# Light_Sensors.net
KiCad netlist of a schematic drawn in EAGLE
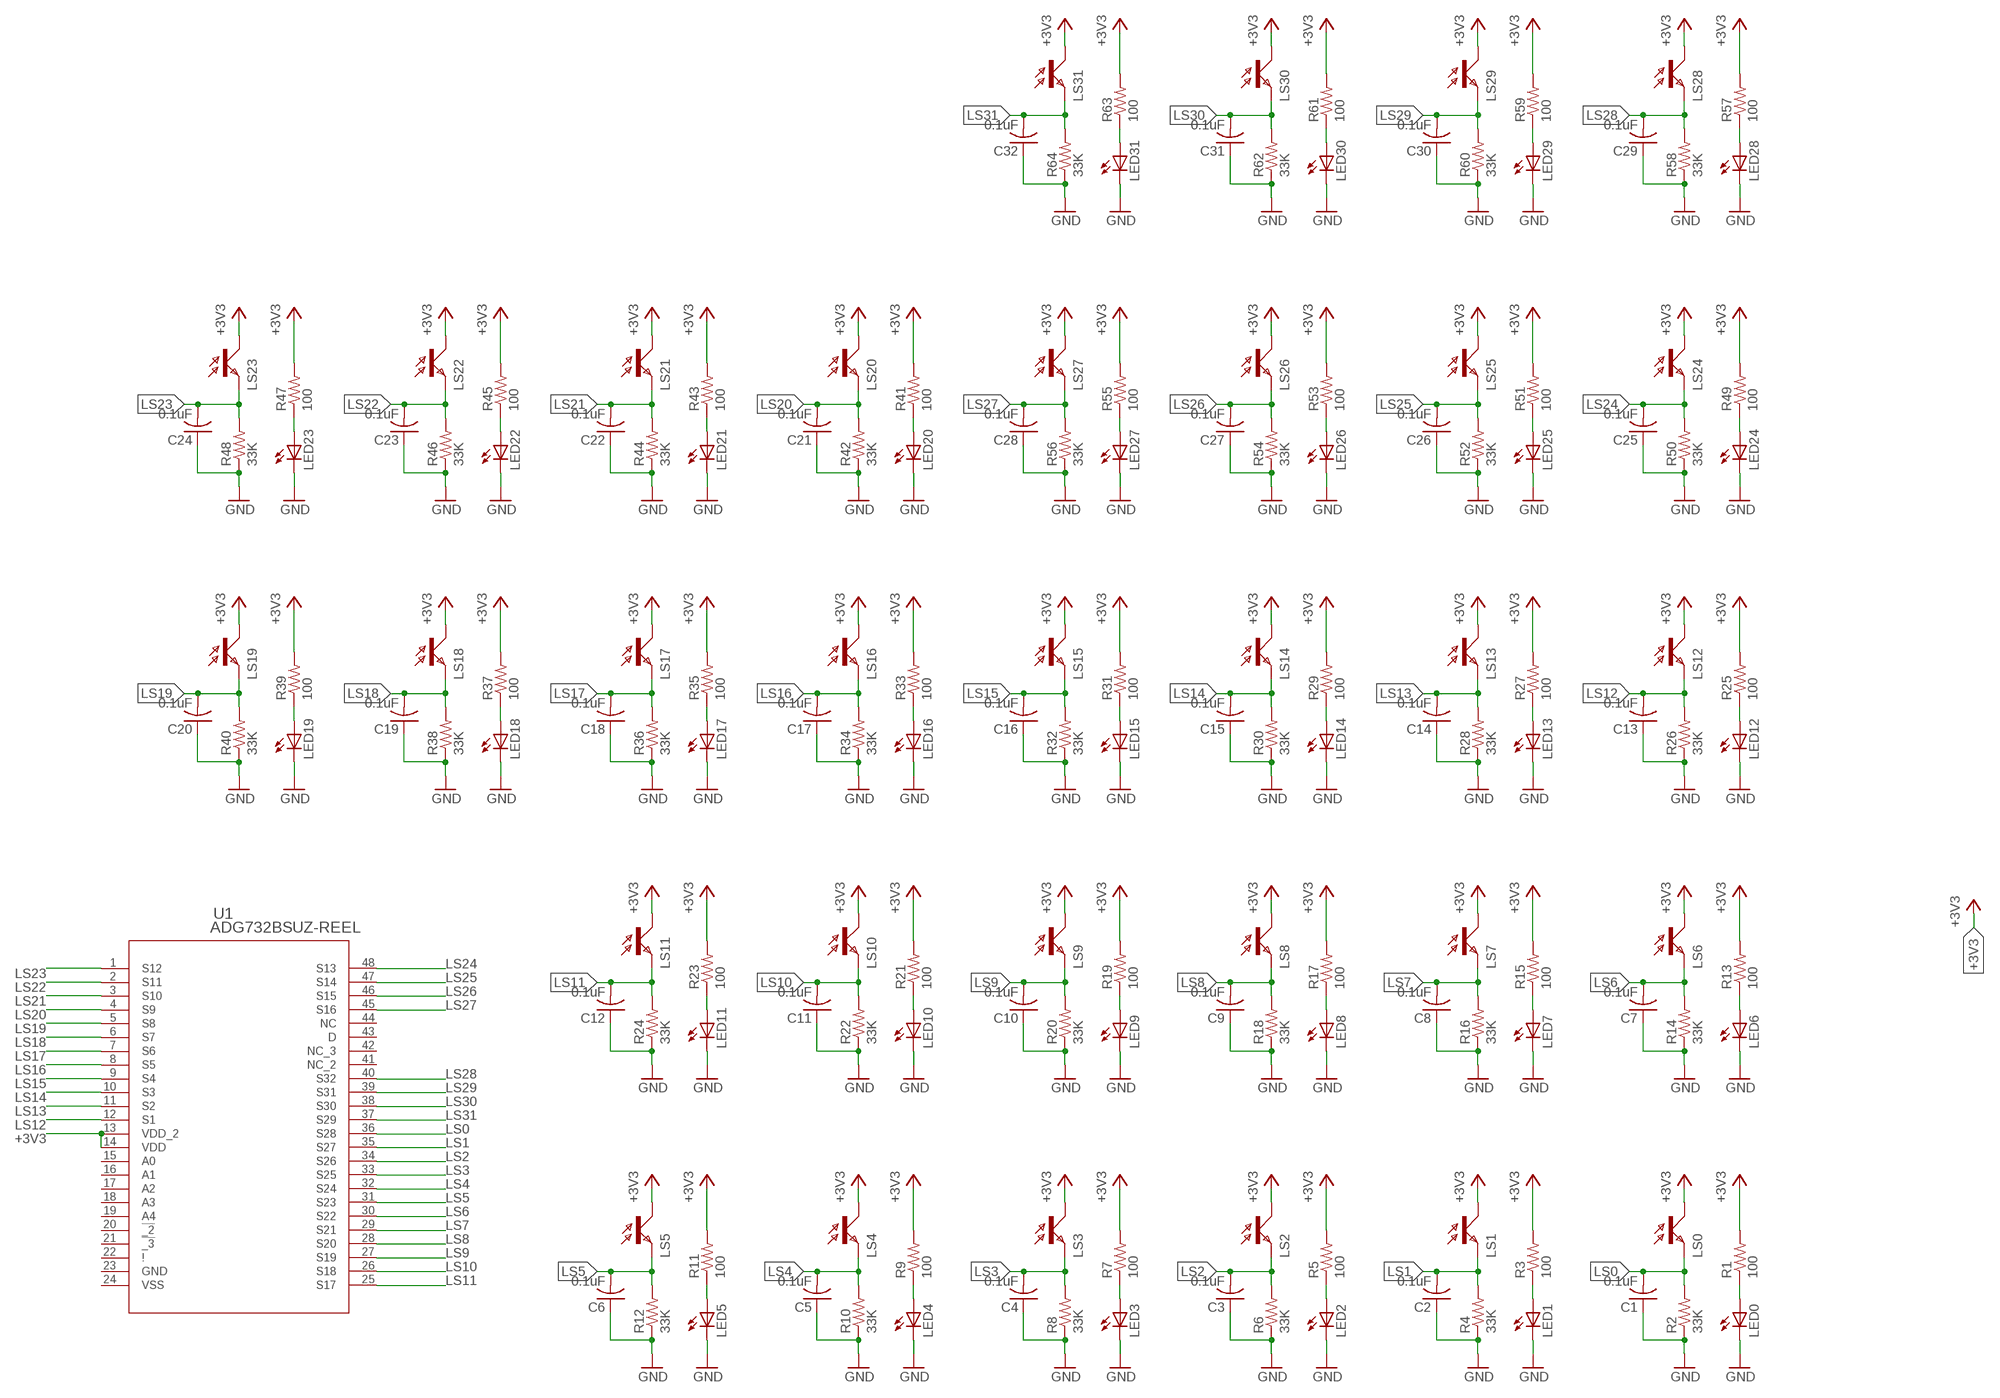
[diagram p0: schematic, sheet 1]

(export (version "E")
  (design (tool "Eeschema 10.0.6"))
  (components
    (comp (ref "C1")
      (value "0.1uF")
      (footprint "eagle-import:C0603")
      (libsource (lib "eagle-import") (part "C-USC0603"))
    )
    (comp (ref "C2")
      (value "0.1uF")
      (footprint "eagle-import:C0603")
      (libsource (lib "eagle-import") (part "C-USC0603"))
    )
    (comp (ref "C3")
      (value "0.1uF")
      (footprint "eagle-import:C0603")
      (libsource (lib "eagle-import") (part "C-USC0603"))
    )
    (comp (ref "C4")
      (value "0.1uF")
      (footprint "eagle-import:C0603")
      (libsource (lib "eagle-import") (part "C-USC0603"))
    )
    (comp (ref "C5")
      (value "0.1uF")
      (footprint "eagle-import:C0603")
      (libsource (lib "eagle-import") (part "C-USC0603"))
    )
    (comp (ref "C6")
      (value "0.1uF")
      (footprint "eagle-import:C0603")
      (libsource (lib "eagle-import") (part "C-USC0603"))
    )
    (comp (ref "C7")
      (value "0.1uF")
      (footprint "eagle-import:C0603")
      (libsource (lib "eagle-import") (part "C-USC0603"))
    )
    (comp (ref "C8")
      (value "0.1uF")
      (footprint "eagle-import:C0603")
      (libsource (lib "eagle-import") (part "C-USC0603"))
    )
    (comp (ref "C9")
      (value "0.1uF")
      (footprint "eagle-import:C0603")
      (libsource (lib "eagle-import") (part "C-USC0603"))
    )
    (comp (ref "C10")
      (value "0.1uF")
      (footprint "eagle-import:C0603")
      (libsource (lib "eagle-import") (part "C-USC0603"))
    )
    (comp (ref "C11")
      (value "0.1uF")
      (footprint "eagle-import:C0603")
      (libsource (lib "eagle-import") (part "C-USC0603"))
    )
    (comp (ref "C12")
      (value "0.1uF")
      (footprint "eagle-import:C0603")
      (libsource (lib "eagle-import") (part "C-USC0603"))
    )
    (comp (ref "C13")
      (value "0.1uF")
      (footprint "eagle-import:C0603")
      (libsource (lib "eagle-import") (part "C-USC0603"))
    )
    (comp (ref "C14")
      (value "0.1uF")
      (footprint "eagle-import:C0603")
      (libsource (lib "eagle-import") (part "C-USC0603"))
    )
    (comp (ref "C15")
      (value "0.1uF")
      (footprint "eagle-import:C0603")
      (libsource (lib "eagle-import") (part "C-USC0603"))
    )
    (comp (ref "C16")
      (value "0.1uF")
      (footprint "eagle-import:C0603")
      (libsource (lib "eagle-import") (part "C-USC0603"))
    )
    (comp (ref "C17")
      (value "0.1uF")
      (footprint "eagle-import:C0603")
      (libsource (lib "eagle-import") (part "C-USC0603"))
    )
    (comp (ref "C18")
      (value "0.1uF")
      (footprint "eagle-import:C0603")
      (libsource (lib "eagle-import") (part "C-USC0603"))
    )
    (comp (ref "C19")
      (value "0.1uF")
      (footprint "eagle-import:C0603")
      (libsource (lib "eagle-import") (part "C-USC0603"))
    )
    (comp (ref "C20")
      (value "0.1uF")
      (footprint "eagle-import:C0603")
      (libsource (lib "eagle-import") (part "C-USC0603"))
    )
    (comp (ref "C21")
      (value "0.1uF")
      (footprint "eagle-import:C0603")
      (libsource (lib "eagle-import") (part "C-USC0603"))
    )
    (comp (ref "C22")
      (value "0.1uF")
      (footprint "eagle-import:C0603")
      (libsource (lib "eagle-import") (part "C-USC0603"))
    )
    (comp (ref "C23")
      (value "0.1uF")
      (footprint "eagle-import:C0603")
      (libsource (lib "eagle-import") (part "C-USC0603"))
    )
    (comp (ref "C24")
      (value "0.1uF")
      (footprint "eagle-import:C0603")
      (libsource (lib "eagle-import") (part "C-USC0603"))
    )
    (comp (ref "C25")
      (value "0.1uF")
      (footprint "eagle-import:C0603")
      (libsource (lib "eagle-import") (part "C-USC0603"))
    )
    (comp (ref "C26")
      (value "0.1uF")
      (footprint "eagle-import:C0603")
      (libsource (lib "eagle-import") (part "C-USC0603"))
    )
    (comp (ref "C27")
      (value "0.1uF")
      (footprint "eagle-import:C0603")
      (libsource (lib "eagle-import") (part "C-USC0603"))
    )
    (comp (ref "C28")
      (value "0.1uF")
      (footprint "eagle-import:C0603")
      (libsource (lib "eagle-import") (part "C-USC0603"))
    )
    (comp (ref "C29")
      (value "0.1uF")
      (footprint "eagle-import:C0603")
      (libsource (lib "eagle-import") (part "C-USC0603"))
    )
    (comp (ref "C30")
      (value "0.1uF")
      (footprint "eagle-import:C0603")
      (libsource (lib "eagle-import") (part "C-USC0603"))
    )
    (comp (ref "C31")
      (value "0.1uF")
      (footprint "eagle-import:C0603")
      (libsource (lib "eagle-import") (part "C-USC0603"))
    )
    (comp (ref "C32")
      (value "0.1uF")
      (footprint "eagle-import:C0603")
      (libsource (lib "eagle-import") (part "C-USC0603"))
    )
    (comp (ref "LED0")
      (value "LEDCHIPLED_0603")
      (footprint "eagle-import:CHIPLED_0603")
      (libsource (lib "eagle-import") (part "LEDCHIPLED_0603"))
    )
    (comp (ref "LED1")
      (value "LEDCHIPLED_0603")
      (footprint "eagle-import:CHIPLED_0603")
      (libsource (lib "eagle-import") (part "LEDCHIPLED_0603"))
    )
    (comp (ref "LED2")
      (value "LEDCHIPLED_0603")
      (footprint "eagle-import:CHIPLED_0603")
      (libsource (lib "eagle-import") (part "LEDCHIPLED_0603"))
    )
    (comp (ref "LED3")
      (value "LEDCHIPLED_0603")
      (footprint "eagle-import:CHIPLED_0603")
      (libsource (lib "eagle-import") (part "LEDCHIPLED_0603"))
    )
    (comp (ref "LED4")
      (value "LEDCHIPLED_0603")
      (footprint "eagle-import:CHIPLED_0603")
      (libsource (lib "eagle-import") (part "LEDCHIPLED_0603"))
    )
    (comp (ref "LED5")
      (value "LEDCHIPLED_0603")
      (footprint "eagle-import:CHIPLED_0603")
      (libsource (lib "eagle-import") (part "LEDCHIPLED_0603"))
    )
    (comp (ref "LED6")
      (value "LEDCHIPLED_0603")
      (footprint "eagle-import:CHIPLED_0603")
      (libsource (lib "eagle-import") (part "LEDCHIPLED_0603"))
    )
    (comp (ref "LED7")
      (value "LEDCHIPLED_0603")
      (footprint "eagle-import:CHIPLED_0603")
      (libsource (lib "eagle-import") (part "LEDCHIPLED_0603"))
    )
    (comp (ref "LED8")
      (value "LEDCHIPLED_0603")
      (footprint "eagle-import:CHIPLED_0603")
      (libsource (lib "eagle-import") (part "LEDCHIPLED_0603"))
    )
    (comp (ref "LED9")
      (value "LEDCHIPLED_0603")
      (footprint "eagle-import:CHIPLED_0603")
      (libsource (lib "eagle-import") (part "LEDCHIPLED_0603"))
    )
    (comp (ref "LED10")
      (value "LEDCHIPLED_0603")
      (footprint "eagle-import:CHIPLED_0603")
      (libsource (lib "eagle-import") (part "LEDCHIPLED_0603"))
    )
    (comp (ref "LED11")
      (value "LEDCHIPLED_0603")
      (footprint "eagle-import:CHIPLED_0603")
      (libsource (lib "eagle-import") (part "LEDCHIPLED_0603"))
    )
    (comp (ref "LED12")
      (value "LEDCHIPLED_0603")
      (footprint "eagle-import:CHIPLED_0603")
      (libsource (lib "eagle-import") (part "LEDCHIPLED_0603"))
    )
    (comp (ref "LED13")
      (value "LEDCHIPLED_0603")
      (footprint "eagle-import:CHIPLED_0603")
      (libsource (lib "eagle-import") (part "LEDCHIPLED_0603"))
    )
    (comp (ref "LED14")
      (value "LEDCHIPLED_0603")
      (footprint "eagle-import:CHIPLED_0603")
      (libsource (lib "eagle-import") (part "LEDCHIPLED_0603"))
    )
    (comp (ref "LED15")
      (value "LEDCHIPLED_0603")
      (footprint "eagle-import:CHIPLED_0603")
      (libsource (lib "eagle-import") (part "LEDCHIPLED_0603"))
    )
    (comp (ref "LED16")
      (value "LEDCHIPLED_0603")
      (footprint "eagle-import:CHIPLED_0603")
      (libsource (lib "eagle-import") (part "LEDCHIPLED_0603"))
    )
    (comp (ref "LED17")
      (value "LEDCHIPLED_0603")
      (footprint "eagle-import:CHIPLED_0603")
      (libsource (lib "eagle-import") (part "LEDCHIPLED_0603"))
    )
    (comp (ref "LED18")
      (value "LEDCHIPLED_0603")
      (footprint "eagle-import:CHIPLED_0603")
      (libsource (lib "eagle-import") (part "LEDCHIPLED_0603"))
    )
    (comp (ref "LED19")
      (value "LEDCHIPLED_0603")
      (footprint "eagle-import:CHIPLED_0603")
      (libsource (lib "eagle-import") (part "LEDCHIPLED_0603"))
    )
    (comp (ref "LED20")
      (value "LEDCHIPLED_0603")
      (footprint "eagle-import:CHIPLED_0603")
      (libsource (lib "eagle-import") (part "LEDCHIPLED_0603"))
    )
    (comp (ref "LED21")
      (value "LEDCHIPLED_0603")
      (footprint "eagle-import:CHIPLED_0603")
      (libsource (lib "eagle-import") (part "LEDCHIPLED_0603"))
    )
    (comp (ref "LED22")
      (value "LEDCHIPLED_0603")
      (footprint "eagle-import:CHIPLED_0603")
      (libsource (lib "eagle-import") (part "LEDCHIPLED_0603"))
    )
    (comp (ref "LED23")
      (value "LEDCHIPLED_0603")
      (footprint "eagle-import:CHIPLED_0603")
      (libsource (lib "eagle-import") (part "LEDCHIPLED_0603"))
    )
    (comp (ref "LED24")
      (value "LEDCHIPLED_0603")
      (footprint "eagle-import:CHIPLED_0603")
      (libsource (lib "eagle-import") (part "LEDCHIPLED_0603"))
    )
    (comp (ref "LED25")
      (value "LEDCHIPLED_0603")
      (footprint "eagle-import:CHIPLED_0603")
      (libsource (lib "eagle-import") (part "LEDCHIPLED_0603"))
    )
    (comp (ref "LED26")
      (value "LEDCHIPLED_0603")
      (footprint "eagle-import:CHIPLED_0603")
      (libsource (lib "eagle-import") (part "LEDCHIPLED_0603"))
    )
    (comp (ref "LED27")
      (value "LEDCHIPLED_0603")
      (footprint "eagle-import:CHIPLED_0603")
      (libsource (lib "eagle-import") (part "LEDCHIPLED_0603"))
    )
    (comp (ref "LED28")
      (value "LEDCHIPLED_0603")
      (footprint "eagle-import:CHIPLED_0603")
      (libsource (lib "eagle-import") (part "LEDCHIPLED_0603"))
    )
    (comp (ref "LED29")
      (value "LEDCHIPLED_0603")
      (footprint "eagle-import:CHIPLED_0603")
      (libsource (lib "eagle-import") (part "LEDCHIPLED_0603"))
    )
    (comp (ref "LED30")
      (value "LEDCHIPLED_0603")
      (footprint "eagle-import:CHIPLED_0603")
      (libsource (lib "eagle-import") (part "LEDCHIPLED_0603"))
    )
    (comp (ref "LED31")
      (value "LEDCHIPLED_0603")
      (footprint "eagle-import:CHIPLED_0603")
      (libsource (lib "eagle-import") (part "LEDCHIPLED_0603"))
    )
    (comp (ref "LS0")
      (value "ALS")
      (footprint "eagle-import:SMD")
      (libsource (lib "eagle-import") (part "ALS"))
    )
    (comp (ref "LS1")
      (value "ALS")
      (footprint "eagle-import:SMD")
      (libsource (lib "eagle-import") (part "ALS"))
    )
    (comp (ref "LS2")
      (value "ALS")
      (footprint "eagle-import:SMD")
      (libsource (lib "eagle-import") (part "ALS"))
    )
    (comp (ref "LS3")
      (value "ALS")
      (footprint "eagle-import:SMD")
      (libsource (lib "eagle-import") (part "ALS"))
    )
    (comp (ref "LS4")
      (value "ALS")
      (footprint "eagle-import:SMD")
      (libsource (lib "eagle-import") (part "ALS"))
    )
    (comp (ref "LS5")
      (value "ALS")
      (footprint "eagle-import:SMD")
      (libsource (lib "eagle-import") (part "ALS"))
    )
    (comp (ref "LS6")
      (value "ALS")
      (footprint "eagle-import:SMD")
      (libsource (lib "eagle-import") (part "ALS"))
    )
    (comp (ref "LS7")
      (value "ALS")
      (footprint "eagle-import:SMD")
      (libsource (lib "eagle-import") (part "ALS"))
    )
    (comp (ref "LS8")
      (value "ALS")
      (footprint "eagle-import:SMD")
      (libsource (lib "eagle-import") (part "ALS"))
    )
    (comp (ref "LS9")
      (value "ALS")
      (footprint "eagle-import:SMD")
      (libsource (lib "eagle-import") (part "ALS"))
    )
    (comp (ref "LS10")
      (value "ALS")
      (footprint "eagle-import:SMD")
      (libsource (lib "eagle-import") (part "ALS"))
    )
    (comp (ref "LS11")
      (value "ALS")
      (footprint "eagle-import:SMD")
      (libsource (lib "eagle-import") (part "ALS"))
    )
    (comp (ref "LS12")
      (value "ALS")
      (footprint "eagle-import:SMD")
      (libsource (lib "eagle-import") (part "ALS"))
    )
    (comp (ref "LS13")
      (value "ALS")
      (footprint "eagle-import:SMD")
      (libsource (lib "eagle-import") (part "ALS"))
    )
    (comp (ref "LS14")
      (value "ALS")
      (footprint "eagle-import:SMD")
      (libsource (lib "eagle-import") (part "ALS"))
    )
    (comp (ref "LS15")
      (value "ALS")
      (footprint "eagle-import:SMD")
      (libsource (lib "eagle-import") (part "ALS"))
    )
    (comp (ref "LS16")
      (value "ALS")
      (footprint "eagle-import:SMD")
      (libsource (lib "eagle-import") (part "ALS"))
    )
    (comp (ref "LS17")
      (value "ALS")
      (footprint "eagle-import:SMD")
      (libsource (lib "eagle-import") (part "ALS"))
    )
    (comp (ref "LS18")
      (value "ALS")
      (footprint "eagle-import:SMD")
      (libsource (lib "eagle-import") (part "ALS"))
    )
    (comp (ref "LS19")
      (value "ALS")
      (footprint "eagle-import:SMD")
      (libsource (lib "eagle-import") (part "ALS"))
    )
    (comp (ref "LS20")
      (value "ALS")
      (footprint "eagle-import:SMD")
      (libsource (lib "eagle-import") (part "ALS"))
    )
    (comp (ref "LS21")
      (value "ALS")
      (footprint "eagle-import:SMD")
      (libsource (lib "eagle-import") (part "ALS"))
    )
    (comp (ref "LS22")
      (value "ALS")
      (footprint "eagle-import:SMD")
      (libsource (lib "eagle-import") (part "ALS"))
    )
    (comp (ref "LS23")
      (value "ALS")
      (footprint "eagle-import:SMD")
      (libsource (lib "eagle-import") (part "ALS"))
    )
    (comp (ref "LS24")
      (value "ALS")
      (footprint "eagle-import:SMD")
      (libsource (lib "eagle-import") (part "ALS"))
    )
    (comp (ref "LS25")
      (value "ALS")
      (footprint "eagle-import:SMD")
      (libsource (lib "eagle-import") (part "ALS"))
    )
    (comp (ref "LS26")
      (value "ALS")
      (footprint "eagle-import:SMD")
      (libsource (lib "eagle-import") (part "ALS"))
    )
    (comp (ref "LS27")
      (value "ALS")
      (footprint "eagle-import:SMD")
      (libsource (lib "eagle-import") (part "ALS"))
    )
    (comp (ref "LS28")
      (value "ALS")
      (footprint "eagle-import:SMD")
      (libsource (lib "eagle-import") (part "ALS"))
    )
    (comp (ref "LS29")
      (value "ALS")
      (footprint "eagle-import:SMD")
      (libsource (lib "eagle-import") (part "ALS"))
    )
    (comp (ref "LS30")
      (value "ALS")
      (footprint "eagle-import:SMD")
      (libsource (lib "eagle-import") (part "ALS"))
    )
    (comp (ref "LS31")
      (value "ALS")
      (footprint "eagle-import:SMD")
      (libsource (lib "eagle-import") (part "ALS"))
    )
    (comp (ref "R1")
      (value "100")
      (footprint "eagle-import:R0603")
      (libsource (lib "eagle-import") (part "R-US_R0603"))
    )
    (comp (ref "R2")
      (value "33K")
      (footprint "eagle-import:R0603")
      (libsource (lib "eagle-import") (part "R-US_R0603"))
    )
    (comp (ref "R3")
      (value "100")
      (footprint "eagle-import:R0603")
      (libsource (lib "eagle-import") (part "R-US_R0603"))
    )
    (comp (ref "R4")
      (value "33K")
      (footprint "eagle-import:R0603")
      (libsource (lib "eagle-import") (part "R-US_R0603"))
    )
    (comp (ref "R5")
      (value "100")
      (footprint "eagle-import:R0603")
      (libsource (lib "eagle-import") (part "R-US_R0603"))
    )
    (comp (ref "R6")
      (value "33K")
      (footprint "eagle-import:R0603")
      (libsource (lib "eagle-import") (part "R-US_R0603"))
    )
    (comp (ref "R7")
      (value "100")
      (footprint "eagle-import:R0603")
      (libsource (lib "eagle-import") (part "R-US_R0603"))
    )
    (comp (ref "R8")
      (value "33K")
      (footprint "eagle-import:R0603")
      (libsource (lib "eagle-import") (part "R-US_R0603"))
    )
    (comp (ref "R9")
      (value "100")
      (footprint "eagle-import:R0603")
      (libsource (lib "eagle-import") (part "R-US_R0603"))
    )
    (comp (ref "R10")
      (value "33K")
      (footprint "eagle-import:R0603")
      (libsource (lib "eagle-import") (part "R-US_R0603"))
    )
    (comp (ref "R11")
      (value "100")
      (footprint "eagle-import:R0603")
      (libsource (lib "eagle-import") (part "R-US_R0603"))
    )
    (comp (ref "R12")
      (value "33K")
      (footprint "eagle-import:R0603")
      (libsource (lib "eagle-import") (part "R-US_R0603"))
    )
    (comp (ref "R13")
      (value "100")
      (footprint "eagle-import:R0603")
      (libsource (lib "eagle-import") (part "R-US_R0603"))
    )
    (comp (ref "R14")
      (value "33K")
      (footprint "eagle-import:R0603")
      (libsource (lib "eagle-import") (part "R-US_R0603"))
    )
    (comp (ref "R15")
      (value "100")
      (footprint "eagle-import:R0603")
      (libsource (lib "eagle-import") (part "R-US_R0603"))
    )
    (comp (ref "R16")
      (value "33K")
      (footprint "eagle-import:R0603")
      (libsource (lib "eagle-import") (part "R-US_R0603"))
    )
    (comp (ref "R17")
      (value "100")
      (footprint "eagle-import:R0603")
      (libsource (lib "eagle-import") (part "R-US_R0603"))
    )
    (comp (ref "R18")
      (value "33K")
      (footprint "eagle-import:R0603")
      (libsource (lib "eagle-import") (part "R-US_R0603"))
    )
    (comp (ref "R19")
      (value "100")
      (footprint "eagle-import:R0603")
      (libsource (lib "eagle-import") (part "R-US_R0603"))
    )
    (comp (ref "R20")
      (value "33K")
      (footprint "eagle-import:R0603")
      (libsource (lib "eagle-import") (part "R-US_R0603"))
    )
    (comp (ref "R21")
      (value "100")
      (footprint "eagle-import:R0603")
      (libsource (lib "eagle-import") (part "R-US_R0603"))
    )
    (comp (ref "R22")
      (value "33K")
      (footprint "eagle-import:R0603")
      (libsource (lib "eagle-import") (part "R-US_R0603"))
    )
    (comp (ref "R23")
      (value "100")
      (footprint "eagle-import:R0603")
      (libsource (lib "eagle-import") (part "R-US_R0603"))
    )
    (comp (ref "R24")
      (value "33K")
      (footprint "eagle-import:R0603")
      (libsource (lib "eagle-import") (part "R-US_R0603"))
    )
    (comp (ref "R25")
      (value "100")
      (footprint "eagle-import:R0603")
      (libsource (lib "eagle-import") (part "R-US_R0603"))
    )
    (comp (ref "R26")
      (value "33K")
      (footprint "eagle-import:R0603")
      (libsource (lib "eagle-import") (part "R-US_R0603"))
    )
    (comp (ref "R27")
      (value "100")
      (footprint "eagle-import:R0603")
      (libsource (lib "eagle-import") (part "R-US_R0603"))
    )
    (comp (ref "R28")
      (value "33K")
      (footprint "eagle-import:R0603")
      (libsource (lib "eagle-import") (part "R-US_R0603"))
    )
    (comp (ref "R29")
      (value "100")
      (footprint "eagle-import:R0603")
      (libsource (lib "eagle-import") (part "R-US_R0603"))
    )
    (comp (ref "R30")
      (value "33K")
      (footprint "eagle-import:R0603")
      (libsource (lib "eagle-import") (part "R-US_R0603"))
    )
    (comp (ref "R31")
      (value "100")
      (footprint "eagle-import:R0603")
      (libsource (lib "eagle-import") (part "R-US_R0603"))
    )
    (comp (ref "R32")
      (value "33K")
      (footprint "eagle-import:R0603")
      (libsource (lib "eagle-import") (part "R-US_R0603"))
    )
    (comp (ref "R33")
      (value "100")
      (footprint "eagle-import:R0603")
      (libsource (lib "eagle-import") (part "R-US_R0603"))
    )
    (comp (ref "R34")
      (value "33K")
      (footprint "eagle-import:R0603")
      (libsource (lib "eagle-import") (part "R-US_R0603"))
    )
    (comp (ref "R35")
      (value "100")
      (footprint "eagle-import:R0603")
      (libsource (lib "eagle-import") (part "R-US_R0603"))
    )
    (comp (ref "R36")
      (value "33K")
      (footprint "eagle-import:R0603")
      (libsource (lib "eagle-import") (part "R-US_R0603"))
    )
    (comp (ref "R37")
      (value "100")
      (footprint "eagle-import:R0603")
      (libsource (lib "eagle-import") (part "R-US_R0603"))
    )
    (comp (ref "R38")
      (value "33K")
      (footprint "eagle-import:R0603")
      (libsource (lib "eagle-import") (part "R-US_R0603"))
    )
    (comp (ref "R39")
      (value "100")
      (footprint "eagle-import:R0603")
      (libsource (lib "eagle-import") (part "R-US_R0603"))
    )
    (comp (ref "R40")
      (value "33K")
      (footprint "eagle-import:R0603")
      (libsource (lib "eagle-import") (part "R-US_R0603"))
    )
    (comp (ref "R41")
      (value "100")
      (footprint "eagle-import:R0603")
      (libsource (lib "eagle-import") (part "R-US_R0603"))
    )
    (comp (ref "R42")
      (value "33K")
      (footprint "eagle-import:R0603")
      (libsource (lib "eagle-import") (part "R-US_R0603"))
    )
    (comp (ref "R43")
      (value "100")
      (footprint "eagle-import:R0603")
      (libsource (lib "eagle-import") (part "R-US_R0603"))
    )
    (comp (ref "R44")
      (value "33K")
      (footprint "eagle-import:R0603")
      (libsource (lib "eagle-import") (part "R-US_R0603"))
    )
    (comp (ref "R45")
      (value "100")
      (footprint "eagle-import:R0603")
      (libsource (lib "eagle-import") (part "R-US_R0603"))
    )
    (comp (ref "R46")
      (value "33K")
      (footprint "eagle-import:R0603")
      (libsource (lib "eagle-import") (part "R-US_R0603"))
    )
    (comp (ref "R47")
      (value "100")
      (footprint "eagle-import:R0603")
      (libsource (lib "eagle-import") (part "R-US_R0603"))
    )
    (comp (ref "R48")
      (value "33K")
      (footprint "eagle-import:R0603")
      (libsource (lib "eagle-import") (part "R-US_R0603"))
    )
    (comp (ref "R49")
      (value "100")
      (footprint "eagle-import:R0603")
      (libsource (lib "eagle-import") (part "R-US_R0603"))
    )
    (comp (ref "R50")
      (value "33K")
      (footprint "eagle-import:R0603")
      (libsource (lib "eagle-import") (part "R-US_R0603"))
    )
    (comp (ref "R51")
      (value "100")
      (footprint "eagle-import:R0603")
      (libsource (lib "eagle-import") (part "R-US_R0603"))
    )
    (comp (ref "R52")
      (value "33K")
      (footprint "eagle-import:R0603")
      (libsource (lib "eagle-import") (part "R-US_R0603"))
    )
    (comp (ref "R53")
      (value "100")
      (footprint "eagle-import:R0603")
      (libsource (lib "eagle-import") (part "R-US_R0603"))
    )
    (comp (ref "R54")
      (value "33K")
      (footprint "eagle-import:R0603")
      (libsource (lib "eagle-import") (part "R-US_R0603"))
    )
    (comp (ref "R55")
      (value "100")
      (footprint "eagle-import:R0603")
      (libsource (lib "eagle-import") (part "R-US_R0603"))
    )
    (comp (ref "R56")
      (value "33K")
      (footprint "eagle-import:R0603")
      (libsource (lib "eagle-import") (part "R-US_R0603"))
    )
    (comp (ref "R57")
      (value "100")
      (footprint "eagle-import:R0603")
      (libsource (lib "eagle-import") (part "R-US_R0603"))
    )
    (comp (ref "R58")
      (value "33K")
      (footprint "eagle-import:R0603")
      (libsource (lib "eagle-import") (part "R-US_R0603"))
    )
    (comp (ref "R59")
      (value "100")
      (footprint "eagle-import:R0603")
      (libsource (lib "eagle-import") (part "R-US_R0603"))
    )
    (comp (ref "R60")
      (value "33K")
      (footprint "eagle-import:R0603")
      (libsource (lib "eagle-import") (part "R-US_R0603"))
    )
    (comp (ref "R61")
      (value "100")
      (footprint "eagle-import:R0603")
      (libsource (lib "eagle-import") (part "R-US_R0603"))
    )
    (comp (ref "R62")
      (value "33K")
      (footprint "eagle-import:R0603")
      (libsource (lib "eagle-import") (part "R-US_R0603"))
    )
    (comp (ref "R63")
      (value "100")
      (footprint "eagle-import:R0603")
      (libsource (lib "eagle-import") (part "R-US_R0603"))
    )
    (comp (ref "R64")
      (value "33K")
      (footprint "eagle-import:R0603")
      (libsource (lib "eagle-import") (part "R-US_R0603"))
    )
    (comp (ref "U1")
      (value "ADG732BSUZ-REEL")
      (footprint "eagle-import:SU_48")
      (fields (field (name "MANUFACTURER_PART_NUMBER") "ADG732BSUZREEL"))
      (libsource (lib "eagle-import") (part "ADG732BSUZ-REEL"))
    )
  )
  (nets
    (net (code "1") (name "+3V3") (class "Default")
      (node (ref "LS0") (pin "C") (pinfunction "C_C") (pintype "passive"))
      (node (ref "LS1") (pin "C") (pinfunction "C_C") (pintype "passive"))
      (node (ref "LS10") (pin "C") (pinfunction "C_C") (pintype "passive"))
      (node (ref "LS11") (pin "C") (pinfunction "C_C") (pintype "passive"))
      (node (ref "LS12") (pin "C") (pinfunction "C_C") (pintype "passive"))
      (node (ref "LS13") (pin "C") (pinfunction "C_C") (pintype "passive"))
      (node (ref "LS14") (pin "C") (pinfunction "C_C") (pintype "passive"))
      (node (ref "LS15") (pin "C") (pinfunction "C_C") (pintype "passive"))
      (node (ref "LS16") (pin "C") (pinfunction "C_C") (pintype "passive"))
      (node (ref "LS17") (pin "C") (pinfunction "C_C") (pintype "passive"))
      (node (ref "LS18") (pin "C") (pinfunction "C_C") (pintype "passive"))
      (node (ref "LS19") (pin "C") (pinfunction "C_C") (pintype "passive"))
      (node (ref "LS2") (pin "C") (pinfunction "C_C") (pintype "passive"))
      (node (ref "LS20") (pin "C") (pinfunction "C_C") (pintype "passive"))
      (node (ref "LS21") (pin "C") (pinfunction "C_C") (pintype "passive"))
      (node (ref "LS22") (pin "C") (pinfunction "C_C") (pintype "passive"))
      (node (ref "LS23") (pin "C") (pinfunction "C_C") (pintype "passive"))
      (node (ref "LS24") (pin "C") (pinfunction "C_C") (pintype "passive"))
      (node (ref "LS25") (pin "C") (pinfunction "C_C") (pintype "passive"))
      (node (ref "LS26") (pin "C") (pinfunction "C_C") (pintype "passive"))
      (node (ref "LS27") (pin "C") (pinfunction "C_C") (pintype "passive"))
      (node (ref "LS28") (pin "C") (pinfunction "C_C") (pintype "passive"))
      (node (ref "LS29") (pin "C") (pinfunction "C_C") (pintype "passive"))
      (node (ref "LS3") (pin "C") (pinfunction "C_C") (pintype "passive"))
      (node (ref "LS30") (pin "C") (pinfunction "C_C") (pintype "passive"))
      (node (ref "LS31") (pin "C") (pinfunction "C_C") (pintype "passive"))
      (node (ref "LS4") (pin "C") (pinfunction "C_C") (pintype "passive"))
      (node (ref "LS5") (pin "C") (pinfunction "C_C") (pintype "passive"))
      (node (ref "LS6") (pin "C") (pinfunction "C_C") (pintype "passive"))
      (node (ref "LS7") (pin "C") (pinfunction "C_C") (pintype "passive"))
      (node (ref "LS8") (pin "C") (pinfunction "C_C") (pintype "passive"))
      (node (ref "LS9") (pin "C") (pinfunction "C_C") (pintype "passive"))
      (node (ref "R1") (pin "2") (pinfunction "2_2") (pintype "passive"))
      (node (ref "R11") (pin "2") (pinfunction "2_2") (pintype "passive"))
      (node (ref "R13") (pin "2") (pinfunction "2_2") (pintype "passive"))
      (node (ref "R15") (pin "2") (pinfunction "2_2") (pintype "passive"))
      (node (ref "R17") (pin "2") (pinfunction "2_2") (pintype "passive"))
      (node (ref "R19") (pin "2") (pinfunction "2_2") (pintype "passive"))
      (node (ref "R21") (pin "2") (pinfunction "2_2") (pintype "passive"))
      (node (ref "R23") (pin "2") (pinfunction "2_2") (pintype "passive"))
      (node (ref "R25") (pin "2") (pinfunction "2_2") (pintype "passive"))
      (node (ref "R27") (pin "2") (pinfunction "2_2") (pintype "passive"))
      (node (ref "R29") (pin "2") (pinfunction "2_2") (pintype "passive"))
      (node (ref "R3") (pin "2") (pinfunction "2_2") (pintype "passive"))
      (node (ref "R31") (pin "2") (pinfunction "2_2") (pintype "passive"))
      (node (ref "R33") (pin "2") (pinfunction "2_2") (pintype "passive"))
      (node (ref "R35") (pin "2") (pinfunction "2_2") (pintype "passive"))
      (node (ref "R37") (pin "2") (pinfunction "2_2") (pintype "passive"))
      (node (ref "R39") (pin "2") (pinfunction "2_2") (pintype "passive"))
      (node (ref "R41") (pin "2") (pinfunction "2_2") (pintype "passive"))
      (node (ref "R43") (pin "2") (pinfunction "2_2") (pintype "passive"))
      (node (ref "R45") (pin "2") (pinfunction "2_2") (pintype "passive"))
      (node (ref "R47") (pin "2") (pinfunction "2_2") (pintype "passive"))
      (node (ref "R49") (pin "2") (pinfunction "2_2") (pintype "passive"))
      (node (ref "R5") (pin "2") (pinfunction "2_2") (pintype "passive"))
      (node (ref "R51") (pin "2") (pinfunction "2_2") (pintype "passive"))
      (node (ref "R53") (pin "2") (pinfunction "2_2") (pintype "passive"))
      (node (ref "R55") (pin "2") (pinfunction "2_2") (pintype "passive"))
      (node (ref "R57") (pin "2") (pinfunction "2_2") (pintype "passive"))
      (node (ref "R59") (pin "2") (pinfunction "2_2") (pintype "passive"))
      (node (ref "R61") (pin "2") (pinfunction "2_2") (pintype "passive"))
      (node (ref "R63") (pin "2") (pinfunction "2_2") (pintype "passive"))
      (node (ref "R7") (pin "2") (pinfunction "2_2") (pintype "passive"))
      (node (ref "R9") (pin "2") (pinfunction "2_2") (pintype "passive"))
      (node (ref "U1") (pin "13") (pinfunction "VDD_2_13") (pintype "power_in"))
      (node (ref "U1") (pin "14") (pinfunction "VDD_14") (pintype "power_in"))
    )
    (net (code "2") (name "/VSS") (class "Default")
      (node (ref "U1") (pin "24") (pinfunction "VSS_24") (pintype "power_in"))
    )
    (net (code "3") (name "GND") (class "Default")
      (node (ref "C1") (pin "1") (pinfunction "1_1") (pintype "passive"))
      (node (ref "C10") (pin "1") (pinfunction "1_1") (pintype "passive"))
      (node (ref "C11") (pin "1") (pinfunction "1_1") (pintype "passive"))
      (node (ref "C12") (pin "1") (pinfunction "1_1") (pintype "passive"))
      (node (ref "C13") (pin "1") (pinfunction "1_1") (pintype "passive"))
      (node (ref "C14") (pin "1") (pinfunction "1_1") (pintype "passive"))
      (node (ref "C15") (pin "1") (pinfunction "1_1") (pintype "passive"))
      (node (ref "C16") (pin "1") (pinfunction "1_1") (pintype "passive"))
      (node (ref "C17") (pin "1") (pinfunction "1_1") (pintype "passive"))
      (node (ref "C18") (pin "1") (pinfunction "1_1") (pintype "passive"))
      (node (ref "C19") (pin "1") (pinfunction "1_1") (pintype "passive"))
      (node (ref "C2") (pin "1") (pinfunction "1_1") (pintype "passive"))
      (node (ref "C20") (pin "1") (pinfunction "1_1") (pintype "passive"))
      (node (ref "C21") (pin "1") (pinfunction "1_1") (pintype "passive"))
      (node (ref "C22") (pin "1") (pinfunction "1_1") (pintype "passive"))
      (node (ref "C23") (pin "1") (pinfunction "1_1") (pintype "passive"))
      (node (ref "C24") (pin "1") (pinfunction "1_1") (pintype "passive"))
      (node (ref "C25") (pin "1") (pinfunction "1_1") (pintype "passive"))
      (node (ref "C26") (pin "1") (pinfunction "1_1") (pintype "passive"))
      (node (ref "C27") (pin "1") (pinfunction "1_1") (pintype "passive"))
      (node (ref "C28") (pin "1") (pinfunction "1_1") (pintype "passive"))
      (node (ref "C29") (pin "1") (pinfunction "1_1") (pintype "passive"))
      (node (ref "C3") (pin "1") (pinfunction "1_1") (pintype "passive"))
      (node (ref "C30") (pin "1") (pinfunction "1_1") (pintype "passive"))
      (node (ref "C31") (pin "1") (pinfunction "1_1") (pintype "passive"))
      (node (ref "C32") (pin "1") (pinfunction "1_1") (pintype "passive"))
      (node (ref "C4") (pin "1") (pinfunction "1_1") (pintype "passive"))
      (node (ref "C5") (pin "1") (pinfunction "1_1") (pintype "passive"))
      (node (ref "C6") (pin "1") (pinfunction "1_1") (pintype "passive"))
      (node (ref "C7") (pin "1") (pinfunction "1_1") (pintype "passive"))
      (node (ref "C8") (pin "1") (pinfunction "1_1") (pintype "passive"))
      (node (ref "C9") (pin "1") (pinfunction "1_1") (pintype "passive"))
      (node (ref "LED0") (pin "C") (pinfunction "C_C") (pintype "passive"))
      (node (ref "LED1") (pin "C") (pinfunction "C_C") (pintype "passive"))
      (node (ref "LED10") (pin "C") (pinfunction "C_C") (pintype "passive"))
      (node (ref "LED11") (pin "C") (pinfunction "C_C") (pintype "passive"))
      (node (ref "LED12") (pin "C") (pinfunction "C_C") (pintype "passive"))
      (node (ref "LED13") (pin "C") (pinfunction "C_C") (pintype "passive"))
      (node (ref "LED14") (pin "C") (pinfunction "C_C") (pintype "passive"))
      (node (ref "LED15") (pin "C") (pinfunction "C_C") (pintype "passive"))
      (node (ref "LED16") (pin "C") (pinfunction "C_C") (pintype "passive"))
      (node (ref "LED17") (pin "C") (pinfunction "C_C") (pintype "passive"))
      (node (ref "LED18") (pin "C") (pinfunction "C_C") (pintype "passive"))
      (node (ref "LED19") (pin "C") (pinfunction "C_C") (pintype "passive"))
      (node (ref "LED2") (pin "C") (pinfunction "C_C") (pintype "passive"))
      (node (ref "LED20") (pin "C") (pinfunction "C_C") (pintype "passive"))
      (node (ref "LED21") (pin "C") (pinfunction "C_C") (pintype "passive"))
      (node (ref "LED22") (pin "C") (pinfunction "C_C") (pintype "passive"))
      (node (ref "LED23") (pin "C") (pinfunction "C_C") (pintype "passive"))
      (node (ref "LED24") (pin "C") (pinfunction "C_C") (pintype "passive"))
      (node (ref "LED25") (pin "C") (pinfunction "C_C") (pintype "passive"))
      (node (ref "LED26") (pin "C") (pinfunction "C_C") (pintype "passive"))
      (node (ref "LED27") (pin "C") (pinfunction "C_C") (pintype "passive"))
      (node (ref "LED28") (pin "C") (pinfunction "C_C") (pintype "passive"))
      (node (ref "LED29") (pin "C") (pinfunction "C_C") (pintype "passive"))
      (node (ref "LED3") (pin "C") (pinfunction "C_C") (pintype "passive"))
      (node (ref "LED30") (pin "C") (pinfunction "C_C") (pintype "passive"))
      (node (ref "LED31") (pin "C") (pinfunction "C_C") (pintype "passive"))
      (node (ref "LED4") (pin "C") (pinfunction "C_C") (pintype "passive"))
      (node (ref "LED5") (pin "C") (pinfunction "C_C") (pintype "passive"))
      (node (ref "LED6") (pin "C") (pinfunction "C_C") (pintype "passive"))
      (node (ref "LED7") (pin "C") (pinfunction "C_C") (pintype "passive"))
      (node (ref "LED8") (pin "C") (pinfunction "C_C") (pintype "passive"))
      (node (ref "LED9") (pin "C") (pinfunction "C_C") (pintype "passive"))
      (node (ref "R10") (pin "1") (pinfunction "1_1") (pintype "passive"))
      (node (ref "R12") (pin "1") (pinfunction "1_1") (pintype "passive"))
      (node (ref "R14") (pin "1") (pinfunction "1_1") (pintype "passive"))
      (node (ref "R16") (pin "1") (pinfunction "1_1") (pintype "passive"))
      (node (ref "R18") (pin "1") (pinfunction "1_1") (pintype "passive"))
      (node (ref "R2") (pin "1") (pinfunction "1_1") (pintype "passive"))
      (node (ref "R20") (pin "1") (pinfunction "1_1") (pintype "passive"))
      (node (ref "R22") (pin "1") (pinfunction "1_1") (pintype "passive"))
      (node (ref "R24") (pin "1") (pinfunction "1_1") (pintype "passive"))
      (node (ref "R26") (pin "1") (pinfunction "1_1") (pintype "passive"))
      (node (ref "R28") (pin "1") (pinfunction "1_1") (pintype "passive"))
      (node (ref "R30") (pin "1") (pinfunction "1_1") (pintype "passive"))
      (node (ref "R32") (pin "1") (pinfunction "1_1") (pintype "passive"))
      (node (ref "R34") (pin "1") (pinfunction "1_1") (pintype "passive"))
      (node (ref "R36") (pin "1") (pinfunction "1_1") (pintype "passive"))
      (node (ref "R38") (pin "1") (pinfunction "1_1") (pintype "passive"))
      (node (ref "R4") (pin "1") (pinfunction "1_1") (pintype "passive"))
      (node (ref "R40") (pin "1") (pinfunction "1_1") (pintype "passive"))
      (node (ref "R42") (pin "1") (pinfunction "1_1") (pintype "passive"))
      (node (ref "R44") (pin "1") (pinfunction "1_1") (pintype "passive"))
      (node (ref "R46") (pin "1") (pinfunction "1_1") (pintype "passive"))
      (node (ref "R48") (pin "1") (pinfunction "1_1") (pintype "passive"))
      (node (ref "R50") (pin "1") (pinfunction "1_1") (pintype "passive"))
      (node (ref "R52") (pin "1") (pinfunction "1_1") (pintype "passive"))
      (node (ref "R54") (pin "1") (pinfunction "1_1") (pintype "passive"))
      (node (ref "R56") (pin "1") (pinfunction "1_1") (pintype "passive"))
      (node (ref "R58") (pin "1") (pinfunction "1_1") (pintype "passive"))
      (node (ref "R6") (pin "1") (pinfunction "1_1") (pintype "passive"))
      (node (ref "R60") (pin "1") (pinfunction "1_1") (pintype "passive"))
      (node (ref "R62") (pin "1") (pinfunction "1_1") (pintype "passive"))
      (node (ref "R64") (pin "1") (pinfunction "1_1") (pintype "passive"))
      (node (ref "R8") (pin "1") (pinfunction "1_1") (pintype "passive"))
    )
    (net (code "4") (name "LS0") (class "Default")
      (node (ref "C1") (pin "2") (pinfunction "2_2") (pintype "passive"))
      (node (ref "LS0") (pin "E") (pinfunction "E_E") (pintype "passive"))
      (node (ref "R2") (pin "2") (pinfunction "2_2") (pintype "passive"))
      (node (ref "U1") (pin "36") (pinfunction "S28_36") (pintype "passive"))
    )
    (net (code "5") (name "LS1") (class "Default")
      (node (ref "C2") (pin "2") (pinfunction "2_2") (pintype "passive"))
      (node (ref "LS1") (pin "E") (pinfunction "E_E") (pintype "passive"))
      (node (ref "R4") (pin "2") (pinfunction "2_2") (pintype "passive"))
      (node (ref "U1") (pin "35") (pinfunction "S27_35") (pintype "passive"))
    )
    (net (code "6") (name "LS2") (class "Default")
      (node (ref "C3") (pin "2") (pinfunction "2_2") (pintype "passive"))
      (node (ref "LS2") (pin "E") (pinfunction "E_E") (pintype "passive"))
      (node (ref "R6") (pin "2") (pinfunction "2_2") (pintype "passive"))
      (node (ref "U1") (pin "34") (pinfunction "S26_34") (pintype "passive"))
    )
    (net (code "7") (name "LS3") (class "Default")
      (node (ref "C4") (pin "2") (pinfunction "2_2") (pintype "passive"))
      (node (ref "LS3") (pin "E") (pinfunction "E_E") (pintype "passive"))
      (node (ref "R8") (pin "2") (pinfunction "2_2") (pintype "passive"))
      (node (ref "U1") (pin "33") (pinfunction "S25_33") (pintype "passive"))
    )
    (net (code "8") (name "LS4") (class "Default")
      (node (ref "C5") (pin "2") (pinfunction "2_2") (pintype "passive"))
      (node (ref "LS4") (pin "E") (pinfunction "E_E") (pintype "passive"))
      (node (ref "R10") (pin "2") (pinfunction "2_2") (pintype "passive"))
      (node (ref "U1") (pin "32") (pinfunction "S24_32") (pintype "passive"))
    )
    (net (code "9") (name "LS5") (class "Default")
      (node (ref "C6") (pin "2") (pinfunction "2_2") (pintype "passive"))
      (node (ref "LS5") (pin "E") (pinfunction "E_E") (pintype "passive"))
      (node (ref "R12") (pin "2") (pinfunction "2_2") (pintype "passive"))
      (node (ref "U1") (pin "31") (pinfunction "S23_31") (pintype "passive"))
    )
    (net (code "10") (name "LS6") (class "Default")
      (node (ref "C7") (pin "2") (pinfunction "2_2") (pintype "passive"))
      (node (ref "LS6") (pin "E") (pinfunction "E_E") (pintype "passive"))
      (node (ref "R14") (pin "2") (pinfunction "2_2") (pintype "passive"))
      (node (ref "U1") (pin "30") (pinfunction "S22_30") (pintype "passive"))
    )
    (net (code "11") (name "LS7") (class "Default")
      (node (ref "C8") (pin "2") (pinfunction "2_2") (pintype "passive"))
      (node (ref "LS7") (pin "E") (pinfunction "E_E") (pintype "passive"))
      (node (ref "R16") (pin "2") (pinfunction "2_2") (pintype "passive"))
      (node (ref "U1") (pin "29") (pinfunction "S21_29") (pintype "passive"))
    )
    (net (code "12") (name "LS8") (class "Default")
      (node (ref "C9") (pin "2") (pinfunction "2_2") (pintype "passive"))
      (node (ref "LS8") (pin "E") (pinfunction "E_E") (pintype "passive"))
      (node (ref "R18") (pin "2") (pinfunction "2_2") (pintype "passive"))
      (node (ref "U1") (pin "28") (pinfunction "S20_28") (pintype "passive"))
    )
    (net (code "13") (name "LS9") (class "Default")
      (node (ref "C10") (pin "2") (pinfunction "2_2") (pintype "passive"))
      (node (ref "LS9") (pin "E") (pinfunction "E_E") (pintype "passive"))
      (node (ref "R20") (pin "2") (pinfunction "2_2") (pintype "passive"))
      (node (ref "U1") (pin "27") (pinfunction "S19_27") (pintype "passive"))
    )
    (net (code "14") (name "LS10") (class "Default")
      (node (ref "C11") (pin "2") (pinfunction "2_2") (pintype "passive"))
      (node (ref "LS10") (pin "E") (pinfunction "E_E") (pintype "passive"))
      (node (ref "R22") (pin "2") (pinfunction "2_2") (pintype "passive"))
      (node (ref "U1") (pin "26") (pinfunction "S18_26") (pintype "passive"))
    )
    (net (code "15") (name "LS11") (class "Default")
      (node (ref "C12") (pin "2") (pinfunction "2_2") (pintype "passive"))
      (node (ref "LS11") (pin "E") (pinfunction "E_E") (pintype "passive"))
      (node (ref "R24") (pin "2") (pinfunction "2_2") (pintype "passive"))
      (node (ref "U1") (pin "25") (pinfunction "S17_25") (pintype "passive"))
    )
    (net (code "16") (name "LS12") (class "Default")
      (node (ref "C13") (pin "2") (pinfunction "2_2") (pintype "passive"))
      (node (ref "LS12") (pin "E") (pinfunction "E_E") (pintype "passive"))
      (node (ref "R26") (pin "2") (pinfunction "2_2") (pintype "passive"))
      (node (ref "U1") (pin "12") (pinfunction "S1_12") (pintype "passive"))
    )
    (net (code "17") (name "LS13") (class "Default")
      (node (ref "C14") (pin "2") (pinfunction "2_2") (pintype "passive"))
      (node (ref "LS13") (pin "E") (pinfunction "E_E") (pintype "passive"))
      (node (ref "R28") (pin "2") (pinfunction "2_2") (pintype "passive"))
      (node (ref "U1") (pin "11") (pinfunction "S2_11") (pintype "passive"))
    )
    (net (code "18") (name "LS14") (class "Default")
      (node (ref "C15") (pin "2") (pinfunction "2_2") (pintype "passive"))
      (node (ref "LS14") (pin "E") (pinfunction "E_E") (pintype "passive"))
      (node (ref "R30") (pin "2") (pinfunction "2_2") (pintype "passive"))
      (node (ref "U1") (pin "10") (pinfunction "S3_10") (pintype "passive"))
    )
    (net (code "19") (name "LS15") (class "Default")
      (node (ref "C16") (pin "2") (pinfunction "2_2") (pintype "passive"))
      (node (ref "LS15") (pin "E") (pinfunction "E_E") (pintype "passive"))
      (node (ref "R32") (pin "2") (pinfunction "2_2") (pintype "passive"))
      (node (ref "U1") (pin "9") (pinfunction "S4_9") (pintype "passive"))
    )
    (net (code "20") (name "LS16") (class "Default")
      (node (ref "C17") (pin "2") (pinfunction "2_2") (pintype "passive"))
      (node (ref "LS16") (pin "E") (pinfunction "E_E") (pintype "passive"))
      (node (ref "R34") (pin "2") (pinfunction "2_2") (pintype "passive"))
      (node (ref "U1") (pin "8") (pinfunction "S5_8") (pintype "passive"))
    )
    (net (code "21") (name "LS17") (class "Default")
      (node (ref "C18") (pin "2") (pinfunction "2_2") (pintype "passive"))
      (node (ref "LS17") (pin "E") (pinfunction "E_E") (pintype "passive"))
      (node (ref "R36") (pin "2") (pinfunction "2_2") (pintype "passive"))
      (node (ref "U1") (pin "7") (pinfunction "S6_7") (pintype "passive"))
    )
    (net (code "22") (name "LS18") (class "Default")
      (node (ref "C19") (pin "2") (pinfunction "2_2") (pintype "passive"))
      (node (ref "LS18") (pin "E") (pinfunction "E_E") (pintype "passive"))
      (node (ref "R38") (pin "2") (pinfunction "2_2") (pintype "passive"))
      (node (ref "U1") (pin "6") (pinfunction "S7_6") (pintype "passive"))
    )
    (net (code "23") (name "LS19") (class "Default")
      (node (ref "C20") (pin "2") (pinfunction "2_2") (pintype "passive"))
      (node (ref "LS19") (pin "E") (pinfunction "E_E") (pintype "passive"))
      (node (ref "R40") (pin "2") (pinfunction "2_2") (pintype "passive"))
      (node (ref "U1") (pin "5") (pinfunction "S8_5") (pintype "passive"))
    )
    (net (code "24") (name "LS20") (class "Default")
      (node (ref "C21") (pin "2") (pinfunction "2_2") (pintype "passive"))
      (node (ref "LS20") (pin "E") (pinfunction "E_E") (pintype "passive"))
      (node (ref "R42") (pin "2") (pinfunction "2_2") (pintype "passive"))
      (node (ref "U1") (pin "4") (pinfunction "S9_4") (pintype "passive"))
    )
    (net (code "25") (name "LS21") (class "Default")
      (node (ref "C22") (pin "2") (pinfunction "2_2") (pintype "passive"))
      (node (ref "LS21") (pin "E") (pinfunction "E_E") (pintype "passive"))
      (node (ref "R44") (pin "2") (pinfunction "2_2") (pintype "passive"))
      (node (ref "U1") (pin "3") (pinfunction "S10_3") (pintype "passive"))
    )
    (net (code "26") (name "LS22") (class "Default")
      (node (ref "C23") (pin "2") (pinfunction "2_2") (pintype "passive"))
      (node (ref "LS22") (pin "E") (pinfunction "E_E") (pintype "passive"))
      (node (ref "R46") (pin "2") (pinfunction "2_2") (pintype "passive"))
      (node (ref "U1") (pin "2") (pinfunction "S11_2") (pintype "passive"))
    )
    (net (code "27") (name "LS23") (class "Default")
      (node (ref "C24") (pin "2") (pinfunction "2_2") (pintype "passive"))
      (node (ref "LS23") (pin "E") (pinfunction "E_E") (pintype "passive"))
      (node (ref "R48") (pin "2") (pinfunction "2_2") (pintype "passive"))
      (node (ref "U1") (pin "1") (pinfunction "S12_1") (pintype "passive"))
    )
    (net (code "28") (name "LS24") (class "Default")
      (node (ref "C25") (pin "2") (pinfunction "2_2") (pintype "passive"))
      (node (ref "LS24") (pin "E") (pinfunction "E_E") (pintype "passive"))
      (node (ref "R50") (pin "2") (pinfunction "2_2") (pintype "passive"))
      (node (ref "U1") (pin "48") (pinfunction "S13_48") (pintype "passive"))
    )
    (net (code "29") (name "LS25") (class "Default")
      (node (ref "C26") (pin "2") (pinfunction "2_2") (pintype "passive"))
      (node (ref "LS25") (pin "E") (pinfunction "E_E") (pintype "passive"))
      (node (ref "R52") (pin "2") (pinfunction "2_2") (pintype "passive"))
      (node (ref "U1") (pin "47") (pinfunction "S14_47") (pintype "passive"))
    )
    (net (code "30") (name "LS26") (class "Default")
      (node (ref "C27") (pin "2") (pinfunction "2_2") (pintype "passive"))
      (node (ref "LS26") (pin "E") (pinfunction "E_E") (pintype "passive"))
      (node (ref "R54") (pin "2") (pinfunction "2_2") (pintype "passive"))
      (node (ref "U1") (pin "46") (pinfunction "S15_46") (pintype "passive"))
    )
    (net (code "31") (name "LS27") (class "Default")
      (node (ref "C28") (pin "2") (pinfunction "2_2") (pintype "passive"))
      (node (ref "LS27") (pin "E") (pinfunction "E_E") (pintype "passive"))
      (node (ref "R56") (pin "2") (pinfunction "2_2") (pintype "passive"))
      (node (ref "U1") (pin "45") (pinfunction "S16_45") (pintype "passive"))
    )
    (net (code "32") (name "LS28") (class "Default")
      (node (ref "C29") (pin "2") (pinfunction "2_2") (pintype "passive"))
      (node (ref "LS28") (pin "E") (pinfunction "E_E") (pintype "passive"))
      (node (ref "R58") (pin "2") (pinfunction "2_2") (pintype "passive"))
      (node (ref "U1") (pin "40") (pinfunction "S32_40") (pintype "passive"))
    )
    (net (code "33") (name "LS29") (class "Default")
      (node (ref "C30") (pin "2") (pinfunction "2_2") (pintype "passive"))
      (node (ref "LS29") (pin "E") (pinfunction "E_E") (pintype "passive"))
      (node (ref "R60") (pin "2") (pinfunction "2_2") (pintype "passive"))
      (node (ref "U1") (pin "39") (pinfunction "S31_39") (pintype "passive"))
    )
    (net (code "34") (name "LS30") (class "Default")
      (node (ref "C31") (pin "2") (pinfunction "2_2") (pintype "passive"))
      (node (ref "LS30") (pin "E") (pinfunction "E_E") (pintype "passive"))
      (node (ref "R62") (pin "2") (pinfunction "2_2") (pintype "passive"))
      (node (ref "U1") (pin "38") (pinfunction "S30_38") (pintype "passive"))
    )
    (net (code "35") (name "LS31") (class "Default")
      (node (ref "C32") (pin "2") (pinfunction "2_2") (pintype "passive"))
      (node (ref "LS31") (pin "E") (pinfunction "E_E") (pintype "passive"))
      (node (ref "R64") (pin "2") (pinfunction "2_2") (pintype "passive"))
      (node (ref "U1") (pin "37") (pinfunction "S29_37") (pintype "passive"))
    )
    (net (code "36") (name "Net-(LED0-PadA)") (class "Default")
      (node (ref "LED0") (pin "A") (pinfunction "A_A") (pintype "passive"))
      (node (ref "R1") (pin "1") (pinfunction "1_1") (pintype "passive"))
    )
    (net (code "37") (name "Net-(LED1-PadA)") (class "Default")
      (node (ref "LED1") (pin "A") (pinfunction "A_A") (pintype "passive"))
      (node (ref "R3") (pin "1") (pinfunction "1_1") (pintype "passive"))
    )
    (net (code "38") (name "Net-(LED2-PadA)") (class "Default")
      (node (ref "LED2") (pin "A") (pinfunction "A_A") (pintype "passive"))
      (node (ref "R5") (pin "1") (pinfunction "1_1") (pintype "passive"))
    )
    (net (code "39") (name "Net-(LED3-PadA)") (class "Default")
      (node (ref "LED3") (pin "A") (pinfunction "A_A") (pintype "passive"))
      (node (ref "R7") (pin "1") (pinfunction "1_1") (pintype "passive"))
    )
    (net (code "40") (name "Net-(LED4-PadA)") (class "Default")
      (node (ref "LED4") (pin "A") (pinfunction "A_A") (pintype "passive"))
      (node (ref "R9") (pin "1") (pinfunction "1_1") (pintype "passive"))
    )
    (net (code "41") (name "Net-(LED5-PadA)") (class "Default")
      (node (ref "LED5") (pin "A") (pinfunction "A_A") (pintype "passive"))
      (node (ref "R11") (pin "1") (pinfunction "1_1") (pintype "passive"))
    )
    (net (code "42") (name "Net-(LED6-PadA)") (class "Default")
      (node (ref "LED6") (pin "A") (pinfunction "A_A") (pintype "passive"))
      (node (ref "R13") (pin "1") (pinfunction "1_1") (pintype "passive"))
    )
    (net (code "43") (name "Net-(LED7-PadA)") (class "Default")
      (node (ref "LED7") (pin "A") (pinfunction "A_A") (pintype "passive"))
      (node (ref "R15") (pin "1") (pinfunction "1_1") (pintype "passive"))
    )
    (net (code "44") (name "Net-(LED8-PadA)") (class "Default")
      (node (ref "LED8") (pin "A") (pinfunction "A_A") (pintype "passive"))
      (node (ref "R17") (pin "1") (pinfunction "1_1") (pintype "passive"))
    )
    (net (code "45") (name "Net-(LED9-PadA)") (class "Default")
      (node (ref "LED9") (pin "A") (pinfunction "A_A") (pintype "passive"))
      (node (ref "R19") (pin "1") (pinfunction "1_1") (pintype "passive"))
    )
    (net (code "46") (name "Net-(LED10-PadA)") (class "Default")
      (node (ref "LED10") (pin "A") (pinfunction "A_A") (pintype "passive"))
      (node (ref "R21") (pin "1") (pinfunction "1_1") (pintype "passive"))
    )
    (net (code "47") (name "Net-(LED11-PadA)") (class "Default")
      (node (ref "LED11") (pin "A") (pinfunction "A_A") (pintype "passive"))
      (node (ref "R23") (pin "1") (pinfunction "1_1") (pintype "passive"))
    )
    (net (code "48") (name "Net-(LED12-PadA)") (class "Default")
      (node (ref "LED12") (pin "A") (pinfunction "A_A") (pintype "passive"))
      (node (ref "R25") (pin "1") (pinfunction "1_1") (pintype "passive"))
    )
    (net (code "49") (name "Net-(LED13-PadA)") (class "Default")
      (node (ref "LED13") (pin "A") (pinfunction "A_A") (pintype "passive"))
      (node (ref "R27") (pin "1") (pinfunction "1_1") (pintype "passive"))
    )
    (net (code "50") (name "Net-(LED14-PadA)") (class "Default")
      (node (ref "LED14") (pin "A") (pinfunction "A_A") (pintype "passive"))
      (node (ref "R29") (pin "1") (pinfunction "1_1") (pintype "passive"))
    )
    (net (code "51") (name "Net-(LED15-PadA)") (class "Default")
      (node (ref "LED15") (pin "A") (pinfunction "A_A") (pintype "passive"))
      (node (ref "R31") (pin "1") (pinfunction "1_1") (pintype "passive"))
    )
    (net (code "52") (name "Net-(LED16-PadA)") (class "Default")
      (node (ref "LED16") (pin "A") (pinfunction "A_A") (pintype "passive"))
      (node (ref "R33") (pin "1") (pinfunction "1_1") (pintype "passive"))
    )
    (net (code "53") (name "Net-(LED17-PadA)") (class "Default")
      (node (ref "LED17") (pin "A") (pinfunction "A_A") (pintype "passive"))
      (node (ref "R35") (pin "1") (pinfunction "1_1") (pintype "passive"))
    )
    (net (code "54") (name "Net-(LED18-PadA)") (class "Default")
      (node (ref "LED18") (pin "A") (pinfunction "A_A") (pintype "passive"))
      (node (ref "R37") (pin "1") (pinfunction "1_1") (pintype "passive"))
    )
    (net (code "55") (name "Net-(LED19-PadA)") (class "Default")
      (node (ref "LED19") (pin "A") (pinfunction "A_A") (pintype "passive"))
      (node (ref "R39") (pin "1") (pinfunction "1_1") (pintype "passive"))
    )
    (net (code "56") (name "Net-(LED20-PadA)") (class "Default")
      (node (ref "LED20") (pin "A") (pinfunction "A_A") (pintype "passive"))
      (node (ref "R41") (pin "1") (pinfunction "1_1") (pintype "passive"))
    )
    (net (code "57") (name "Net-(LED21-PadA)") (class "Default")
      (node (ref "LED21") (pin "A") (pinfunction "A_A") (pintype "passive"))
      (node (ref "R43") (pin "1") (pinfunction "1_1") (pintype "passive"))
    )
    (net (code "58") (name "Net-(LED22-PadA)") (class "Default")
      (node (ref "LED22") (pin "A") (pinfunction "A_A") (pintype "passive"))
      (node (ref "R45") (pin "1") (pinfunction "1_1") (pintype "passive"))
    )
    (net (code "59") (name "Net-(LED23-PadA)") (class "Default")
      (node (ref "LED23") (pin "A") (pinfunction "A_A") (pintype "passive"))
      (node (ref "R47") (pin "1") (pinfunction "1_1") (pintype "passive"))
    )
    (net (code "60") (name "Net-(LED24-PadA)") (class "Default")
      (node (ref "LED24") (pin "A") (pinfunction "A_A") (pintype "passive"))
      (node (ref "R49") (pin "1") (pinfunction "1_1") (pintype "passive"))
    )
    (net (code "61") (name "Net-(LED25-PadA)") (class "Default")
      (node (ref "LED25") (pin "A") (pinfunction "A_A") (pintype "passive"))
      (node (ref "R51") (pin "1") (pinfunction "1_1") (pintype "passive"))
    )
    (net (code "62") (name "Net-(LED26-PadA)") (class "Default")
      (node (ref "LED26") (pin "A") (pinfunction "A_A") (pintype "passive"))
      (node (ref "R53") (pin "1") (pinfunction "1_1") (pintype "passive"))
    )
    (net (code "63") (name "Net-(LED27-PadA)") (class "Default")
      (node (ref "LED27") (pin "A") (pinfunction "A_A") (pintype "passive"))
      (node (ref "R55") (pin "1") (pinfunction "1_1") (pintype "passive"))
    )
    (net (code "64") (name "Net-(LED28-PadA)") (class "Default")
      (node (ref "LED28") (pin "A") (pinfunction "A_A") (pintype "passive"))
      (node (ref "R57") (pin "1") (pinfunction "1_1") (pintype "passive"))
    )
    (net (code "65") (name "Net-(LED29-PadA)") (class "Default")
      (node (ref "LED29") (pin "A") (pinfunction "A_A") (pintype "passive"))
      (node (ref "R59") (pin "1") (pinfunction "1_1") (pintype "passive"))
    )
    (net (code "66") (name "Net-(LED30-PadA)") (class "Default")
      (node (ref "LED30") (pin "A") (pinfunction "A_A") (pintype "passive"))
      (node (ref "R61") (pin "1") (pinfunction "1_1") (pintype "passive"))
    )
    (net (code "67") (name "Net-(LED31-PadA)") (class "Default")
      (node (ref "LED31") (pin "A") (pinfunction "A_A") (pintype "passive"))
      (node (ref "R63") (pin "1") (pinfunction "1_1") (pintype "passive"))
    )
    (net (code "68") (name "unconnected-(U1-A0-Pad15)") (class "Default")
      (node (ref "U1") (pin "15") (pinfunction "A0_15") (pintype "passive"))
    )
    (net (code "69") (name "unconnected-(U1-A1-Pad16)") (class "Default")
      (node (ref "U1") (pin "16") (pinfunction "A1_16") (pintype "passive"))
    )
    (net (code "70") (name "unconnected-(U1-A2-Pad17)") (class "Default")
      (node (ref "U1") (pin "17") (pinfunction "A2_17") (pintype "passive"))
    )
    (net (code "71") (name "unconnected-(U1-A3-Pad18)") (class "Default")
      (node (ref "U1") (pin "18") (pinfunction "A3_18") (pintype "passive"))
    )
    (net (code "72") (name "unconnected-(U1-A4-Pad19)") (class "Default")
      (node (ref "U1") (pin "19") (pinfunction "A4_19") (pintype "passive"))
    )
    (net (code "73") (name "unconnected-(U1-D-Pad43)") (class "Default")
      (node (ref "U1") (pin "43") (pinfunction "D_43") (pintype "passive"))
    )
    (net (code "74") (name "unconnected-(U1-GND-Pad23)") (class "Default")
      (node (ref "U1") (pin "23") (pinfunction "GND_23") (pintype "passive"))
    )
    (net (code "75") (name "unconnected-(U1-NC-Pad44)") (class "Default")
      (node (ref "U1") (pin "44") (pinfunction "NC_44") (pintype "passive"))
    )
    (net (code "76") (name "unconnected-(U1-NC_2-Pad41)") (class "Default")
      (node (ref "U1") (pin "41") (pinfunction "NC_2_41") (pintype "passive"))
    )
    (net (code "77") (name "unconnected-(U1-NC_3-Pad42)") (class "Default")
      (node (ref "U1") (pin "42") (pinfunction "NC_3_42") (pintype "passive"))
    )
    (net (code "78") (name "unconnected-(U1-~-Pad22)") (class "Default")
      (node (ref "U1") (pin "22") (pinfunction "~_22") (pintype "passive"))
    )
    (net (code "79") (name "unconnected-(U1-~{_2}-Pad20)") (class "Default")
      (node (ref "U1") (pin "20") (pinfunction "~{_2}_20") (pintype "passive"))
    )
    (net (code "80") (name "unconnected-(U1-~{_3}-Pad21)") (class "Default")
      (node (ref "U1") (pin "21") (pinfunction "~{_3}_21") (pintype "passive"))
    )
  )
)
